# design.net
KiCad netlist of a schematic drawn in Altium Designer
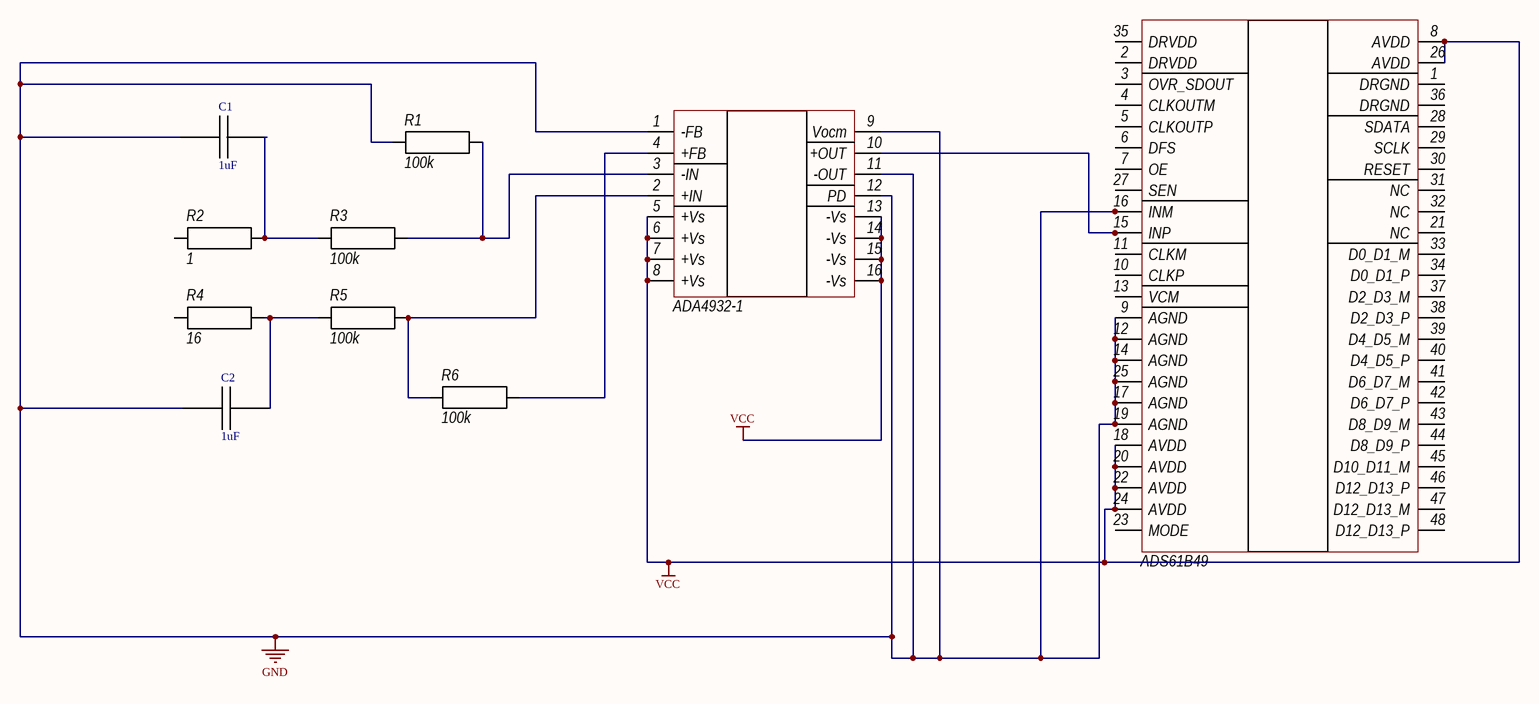
[diagram p0: Принципиальная схема.SchDoc]

(export (version "E")
  (design (tool "Eeschema 10.0.6"))
  (components
    (comp (ref "ADA4932-1")
      (value "ADA4932-1")
      (footprint "CP-16-2")
      (libsource (lib "Library_V_№2") (part "ADA4932-1"))
    )
    (comp (ref "ADS61B49")
      (value "ADS61B49")
      (footprint "VQFN-48")
      (libsource (lib "Library_V_№2") (part "ADS61B49"))
    )
    (comp (ref "C1")
      (value "1uF")
      (footprint "Capasitor10X23")
      (libsource (lib "Library_V_№2") (part "Capasitor"))
    )
    (comp (ref "C2")
      (value "1uF")
      (footprint "Capasitor10X23")
      (libsource (lib "Library_V_№2") (part "Capasitor"))
    )
    (comp (ref "R1") (value "100k") (footprint "SMD 0402") (libsource (lib "Library_V_№2") (part "Resistor")))
    (comp (ref "R2") (value "1") (footprint "SMD 0402") (libsource (lib "Library_V_№2") (part "Resistor")))
    (comp (ref "R3") (value "100k") (footprint "SMD 0402") (libsource (lib "Library_V_№2") (part "Resistor")))
    (comp (ref "R4") (value "16") (footprint "SMD 0402") (libsource (lib "Library_V_№2") (part "Resistor")))
    (comp (ref "R5") (value "100k") (footprint "SMD 0402") (libsource (lib "Library_V_№2") (part "Resistor")))
    (comp (ref "R6") (value "100k") (footprint "SMD 0402") (libsource (lib "Library_V_№2") (part "Resistor")))
  )
  (nets
    (net (code "1") (name "GND") (class "Default")
      (node (ref "ADA4932-1") (pin "1") (pinfunction "-FB_1") (pintype "passive"))
      (node (ref "ADA4932-1") (pin "11") (pinfunction "-OUT_11") (pintype "passive"))
      (node (ref "ADA4932-1") (pin "12") (pinfunction "PD_12") (pintype "passive"))
      (node (ref "ADA4932-1") (pin "9") (pinfunction "Vocm_9") (pintype "passive"))
      (node (ref "ADS61B49") (pin "12") (pinfunction "AGND_12") (pintype "passive"))
      (node (ref "ADS61B49") (pin "14") (pinfunction "AGND_14") (pintype "passive"))
      (node (ref "ADS61B49") (pin "16") (pinfunction "INM_16") (pintype "passive"))
      (node (ref "ADS61B49") (pin "17") (pinfunction "AGND_17") (pintype "passive"))
      (node (ref "ADS61B49") (pin "19") (pinfunction "AGND_19") (pintype "passive"))
      (node (ref "ADS61B49") (pin "25") (pinfunction "AGND_25") (pintype "passive"))
      (node (ref "ADS61B49") (pin "9") (pinfunction "AGND_9") (pintype "passive"))
      (node (ref "C1") (pin "2") (pinfunction "1_2") (pintype "passive"))
      (node (ref "C2") (pin "2") (pinfunction "1_2") (pintype "passive"))
      (node (ref "R1") (pin "1") (pintype "passive"))
    )
    (net (code "2") (name "Net-(ADA4932-1-+FB)") (class "Default")
      (node (ref "ADA4932-1") (pin "4") (pinfunction "+FB_4") (pintype "passive"))
      (node (ref "R6") (pin "2") (pintype "passive"))
    )
    (net (code "3") (name "Net-(ADA4932-1-+IN)") (class "Default")
      (node (ref "ADA4932-1") (pin "2") (pinfunction "+IN_2") (pintype "passive"))
      (node (ref "R5") (pin "2") (pintype "passive"))
      (node (ref "R6") (pin "1") (pintype "passive"))
    )
    (net (code "4") (name "Net-(ADA4932-1-+OUT)") (class "Default")
      (node (ref "ADA4932-1") (pin "10") (pinfunction "+OUT_10") (pintype "passive"))
      (node (ref "ADS61B49") (pin "15") (pinfunction "INP_15") (pintype "passive"))
    )
    (net (code "5") (name "Net-(ADA4932-1--IN)") (class "Default")
      (node (ref "ADA4932-1") (pin "3") (pinfunction "-IN_3") (pintype "passive"))
      (node (ref "R1") (pin "2") (pintype "passive"))
      (node (ref "R3") (pin "2") (pintype "passive"))
    )
    (net (code "6") (name "Net-(C1-0)") (class "Default")
      (node (ref "C1") (pin "1") (pinfunction "0_1") (pintype "passive"))
      (node (ref "R2") (pin "2") (pintype "passive"))
      (node (ref "R3") (pin "1") (pintype "passive"))
    )
    (net (code "7") (name "Net-(C2-0)") (class "Default")
      (node (ref "C2") (pin "1") (pinfunction "0_1") (pintype "passive"))
      (node (ref "R4") (pin "2") (pintype "passive"))
      (node (ref "R5") (pin "1") (pintype "passive"))
    )
    (net (code "8") (name "VCC") (class "Default")
      (node (ref "ADA4932-1") (pin "13") (pinfunction "-Vs_13") (pintype "passive"))
      (node (ref "ADA4932-1") (pin "14") (pinfunction "-Vs_14") (pintype "passive"))
      (node (ref "ADA4932-1") (pin "15") (pinfunction "-Vs_15") (pintype "passive"))
      (node (ref "ADA4932-1") (pin "16") (pinfunction "-Vs_16") (pintype "passive"))
      (node (ref "ADA4932-1") (pin "5") (pinfunction "+Vs_5") (pintype "passive"))
      (node (ref "ADA4932-1") (pin "6") (pinfunction "+Vs_6") (pintype "passive"))
      (node (ref "ADA4932-1") (pin "7") (pinfunction "+Vs_7") (pintype "passive"))
      (node (ref "ADA4932-1") (pin "8") (pinfunction "+Vs_8") (pintype "passive"))
      (node (ref "ADS61B49") (pin "18") (pinfunction "AVDD_18") (pintype "passive"))
      (node (ref "ADS61B49") (pin "20") (pinfunction "AVDD_20") (pintype "passive"))
      (node (ref "ADS61B49") (pin "22") (pinfunction "AVDD_22") (pintype "passive"))
      (node (ref "ADS61B49") (pin "24") (pinfunction "AVDD_24") (pintype "passive"))
      (node (ref "ADS61B49") (pin "26") (pinfunction "AVDD_26") (pintype "passive"))
      (node (ref "ADS61B49") (pin "8") (pinfunction "AVDD_8") (pintype "passive"))
    )
    (net (code "9") (name "unconnected-(ADS61B49-CLKM-Pad11)") (class "Default")
      (node (ref "ADS61B49") (pin "11") (pinfunction "CLKM_11") (pintype "passive"))
    )
    (net (code "10") (name "unconnected-(ADS61B49-CLKOUTM-Pad4)") (class "Default")
      (node (ref "ADS61B49") (pin "4") (pinfunction "CLKOUTM_4") (pintype "passive"))
    )
    (net (code "11") (name "unconnected-(ADS61B49-CLKOUTP-Pad5)") (class "Default")
      (node (ref "ADS61B49") (pin "5") (pinfunction "CLKOUTP_5") (pintype "passive"))
    )
    (net (code "12") (name "unconnected-(ADS61B49-CLKP-Pad10)") (class "Default")
      (node (ref "ADS61B49") (pin "10") (pinfunction "CLKP_10") (pintype "passive"))
    )
    (net (code "13") (name "unconnected-(ADS61B49-D0_D1_M-Pad33)") (class "Default")
      (node (ref "ADS61B49") (pin "33") (pinfunction "D0_D1_M_33") (pintype "passive"))
    )
    (net (code "14") (name "unconnected-(ADS61B49-D0_D1_P-Pad34)") (class "Default")
      (node (ref "ADS61B49") (pin "34") (pinfunction "D0_D1_P_34") (pintype "passive"))
    )
    (net (code "15") (name "unconnected-(ADS61B49-D2_D3_M-Pad37)") (class "Default")
      (node (ref "ADS61B49") (pin "37") (pinfunction "D2_D3_M_37") (pintype "passive"))
    )
    (net (code "16") (name "unconnected-(ADS61B49-D2_D3_P-Pad38)") (class "Default")
      (node (ref "ADS61B49") (pin "38") (pinfunction "D2_D3_P_38") (pintype "passive"))
    )
    (net (code "17") (name "unconnected-(ADS61B49-D4_D5_M-Pad39)") (class "Default")
      (node (ref "ADS61B49") (pin "39") (pinfunction "D4_D5_M_39") (pintype "passive"))
    )
    (net (code "18") (name "unconnected-(ADS61B49-D4_D5_P-Pad40)") (class "Default")
      (node (ref "ADS61B49") (pin "40") (pinfunction "D4_D5_P_40") (pintype "passive"))
    )
    (net (code "19") (name "unconnected-(ADS61B49-D6_D7_M-Pad41)") (class "Default")
      (node (ref "ADS61B49") (pin "41") (pinfunction "D6_D7_M_41") (pintype "passive"))
    )
    (net (code "20") (name "unconnected-(ADS61B49-D6_D7_P-Pad42)") (class "Default")
      (node (ref "ADS61B49") (pin "42") (pinfunction "D6_D7_P_42") (pintype "passive"))
    )
    (net (code "21") (name "unconnected-(ADS61B49-D8_D9_M-Pad43)") (class "Default")
      (node (ref "ADS61B49") (pin "43") (pinfunction "D8_D9_M_43") (pintype "passive"))
    )
    (net (code "22") (name "unconnected-(ADS61B49-D8_D9_P-Pad44)") (class "Default")
      (node (ref "ADS61B49") (pin "44") (pinfunction "D8_D9_P_44") (pintype "passive"))
    )
    (net (code "23") (name "unconnected-(ADS61B49-D10_D11_M-Pad45)") (class "Default")
      (node (ref "ADS61B49") (pin "45") (pinfunction "D10_D11_M_45") (pintype "passive"))
    )
    (net (code "24") (name "unconnected-(ADS61B49-D12_D13_M-Pad47)") (class "Default")
      (node (ref "ADS61B49") (pin "47") (pinfunction "D12_D13_M_47") (pintype "passive"))
    )
    (net (code "25") (name "unconnected-(ADS61B49-D12_D13_P-Pad46)") (class "Default")
      (node (ref "ADS61B49") (pin "46") (pinfunction "D12_D13_P_46") (pintype "passive"))
    )
    (net (code "26") (name "unconnected-(ADS61B49-D12_D13_P-Pad48)") (class "Default")
      (node (ref "ADS61B49") (pin "48") (pinfunction "D12_D13_P_48") (pintype "passive"))
    )
    (net (code "27") (name "unconnected-(ADS61B49-DFS-Pad6)") (class "Default")
      (node (ref "ADS61B49") (pin "6") (pinfunction "DFS_6") (pintype "passive"))
    )
    (net (code "28") (name "unconnected-(ADS61B49-DRGND-Pad1)") (class "Default")
      (node (ref "ADS61B49") (pin "1") (pinfunction "DRGND_1") (pintype "passive"))
    )
    (net (code "29") (name "unconnected-(ADS61B49-DRGND-Pad36)") (class "Default")
      (node (ref "ADS61B49") (pin "36") (pinfunction "DRGND_36") (pintype "passive"))
    )
    (net (code "30") (name "unconnected-(ADS61B49-DRVDD-Pad2)") (class "Default")
      (node (ref "ADS61B49") (pin "2") (pinfunction "DRVDD_2") (pintype "passive"))
    )
    (net (code "31") (name "unconnected-(ADS61B49-DRVDD-Pad35)") (class "Default")
      (node (ref "ADS61B49") (pin "35") (pinfunction "DRVDD_35") (pintype "passive"))
    )
    (net (code "32") (name "unconnected-(ADS61B49-MODE-Pad23)") (class "Default")
      (node (ref "ADS61B49") (pin "23") (pinfunction "MODE_23") (pintype "passive"))
    )
    (net (code "33") (name "unconnected-(ADS61B49-NC-Pad21)") (class "Default")
      (node (ref "ADS61B49") (pin "21") (pinfunction "NC_21") (pintype "passive"))
    )
    (net (code "34") (name "unconnected-(ADS61B49-NC-Pad31)") (class "Default")
      (node (ref "ADS61B49") (pin "31") (pinfunction "NC_31") (pintype "passive"))
    )
    (net (code "35") (name "unconnected-(ADS61B49-NC-Pad32)") (class "Default")
      (node (ref "ADS61B49") (pin "32") (pinfunction "NC_32") (pintype "passive"))
    )
    (net (code "36") (name "unconnected-(ADS61B49-OE-Pad7)") (class "Default")
      (node (ref "ADS61B49") (pin "7") (pinfunction "OE_7") (pintype "passive"))
    )
    (net (code "37") (name "unconnected-(ADS61B49-OVR_SDOUT-Pad3)") (class "Default")
      (node (ref "ADS61B49") (pin "3") (pinfunction "OVR_SDOUT_3") (pintype "passive"))
    )
    (net (code "38") (name "unconnected-(ADS61B49-RESET-Pad30)") (class "Default")
      (node (ref "ADS61B49") (pin "30") (pinfunction "RESET_30") (pintype "passive"))
    )
    (net (code "39") (name "unconnected-(ADS61B49-SCLK-Pad29)") (class "Default")
      (node (ref "ADS61B49") (pin "29") (pinfunction "SCLK_29") (pintype "passive"))
    )
    (net (code "40") (name "unconnected-(ADS61B49-SDATA-Pad28)") (class "Default")
      (node (ref "ADS61B49") (pin "28") (pinfunction "SDATA_28") (pintype "passive"))
    )
    (net (code "41") (name "unconnected-(ADS61B49-SEN-Pad27)") (class "Default")
      (node (ref "ADS61B49") (pin "27") (pinfunction "SEN_27") (pintype "passive"))
    )
    (net (code "42") (name "unconnected-(ADS61B49-VCM-Pad13)") (class "Default")
      (node (ref "ADS61B49") (pin "13") (pinfunction "VCM_13") (pintype "passive"))
    )
    (net (code "43") (name "unconnected-(R2-Pad1)") (class "Default")
      (node (ref "R2") (pin "1") (pintype "passive"))
    )
    (net (code "44") (name "unconnected-(R4-Pad1)") (class "Default")
      (node (ref "R4") (pin "1") (pintype "passive"))
    )
  )
)
